# SH4_-_3_3V_LINEAR_REGULATOR.net
KiCad netlist of a schematic drawn in Altium Designer
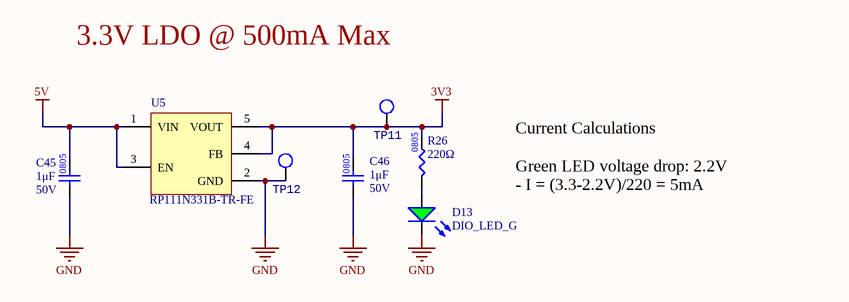
[diagram p0: SH4 - 3.3V LINEAR REGULATOR.SchDoc]

(export (version "E")
  (design (tool "Eeschema 10.0.6"))
  (components
    (comp (ref "C45")
      (value "1μF")
      (footprint "CAP2012")
      (description "CAP CER 1UF 50V X7R 0805")
      (fields
        (field (name "VOLTAGE RATING") "50V")
        (field (name "LCSC PART #") "C28323")
        (field (name "Comment") "CAP_1uF_50V_0805")
      )
      (libsource (lib "UWRT_Schematic_Library_2020") (part "CAP_1uF_50V_0805"))
    )
    (comp (ref "C46")
      (value "1μF")
      (footprint "CAP2012")
      (description "CAP CER 1UF 50V X7R 0805")
      (fields
        (field (name "VOLTAGE RATING") "50V")
        (field (name "LCSC PART #") "C28323")
        (field (name "Comment") "CAP_1uF_50V_0805")
      )
      (libsource (lib "UWRT_Schematic_Library_2020") (part "CAP_1uF_50V_0805"))
    )
    (comp (ref "D13")
      (value "DIO_LED_G")
      (footprint "LED_0805_GREEN")
      (description "LED GREEN DIFFUSED 0805 SMD")
      (libsource (lib "UWRT_Schematic_Library_2020") (part "DIO_LED_G"))
    )
    (comp (ref "R26")
      (value "220Ω")
      (footprint "RES0805")
      (description "RES 220 OHM 5% 1/2W 0805")
      (fields (field (name "LCSC PART #") "C17557") (field (name "Comment") "RES_220Ω_0805_5%"))
      (libsource (lib "UWRT_Schematic_Library_2020") (part "RES_220Ω_0805_5%"))
    )
    (comp (ref "TP11")
      (value "TESTPOINT_LOOP")
      (footprint "TESTPOINT_LOOP")
      (description "TESTPOINT THRUHOLE")
      (libsource (lib "UWRT_Schematic_Library_2020") (part "TESTPOINT_LOOP"))
    )
    (comp (ref "TP12")
      (value "TESTPOINT_LOOP")
      (footprint "TESTPOINT_LOOP")
      (description "TESTPOINT THRUHOLE")
      (libsource (lib "UWRT_Schematic_Library_2020") (part "TESTPOINT_LOOP"))
    )
    (comp (ref "U5")
      (value "LDO_3.3V_500mA")
      (footprint "SOT23-5")
      (description "IC REG LINEAR 3.3V 500MA SOT23-5")
      (fields (field (name "MANUFACTURER PART NUMBER 1") "RP111N331B-TR-FE"))
      (libsource (lib "UWRT_Schematic_Library_2020") (part "LDO_3.3V_500mA"))
    )
  )
  (nets
    (net (code "1") (name "3V3") (class "Default")
      (node (ref "C46") (pin "2") (pinfunction "2_2") (pintype "passive"))
      (node (ref "R26") (pin "2") (pinfunction "2_2") (pintype "passive"))
      (node (ref "TP11") (pin "1") (pintype "passive"))
      (node (ref "U5") (pin "4") (pinfunction "FB_4") (pintype "passive"))
      (node (ref "U5") (pin "5") (pinfunction "VOUT_5") (pintype "passive"))
    )
    (net (code "2") (name "5V") (class "Default")
      (node (ref "C45") (pin "2") (pinfunction "2_2") (pintype "passive"))
      (node (ref "U5") (pin "1") (pinfunction "VIN_1") (pintype "passive"))
      (node (ref "U5") (pin "3") (pinfunction "EN_3") (pintype "passive"))
    )
    (net (code "3") (name "GND") (class "Default")
      (node (ref "C45") (pin "1") (pinfunction "1_1") (pintype "passive"))
      (node (ref "C46") (pin "1") (pinfunction "1_1") (pintype "passive"))
      (node (ref "D13") (pin "2") (pinfunction "K_2") (pintype "passive"))
      (node (ref "TP12") (pin "1") (pintype "passive"))
      (node (ref "U5") (pin "2") (pinfunction "GND_2") (pintype "passive"))
    )
    (net (code "4") (name "Net-(D13-A)") (class "Default")
      (node (ref "D13") (pin "1") (pinfunction "A_1") (pintype "passive"))
      (node (ref "R26") (pin "1") (pinfunction "1_1") (pintype "passive"))
    )
  )
)
